# pufferswitch.net
KiCad netlist of a schematic drawn in EAGLE
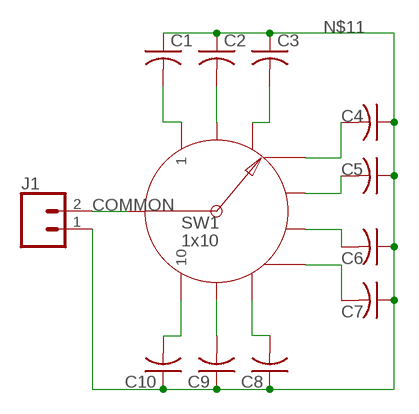
[diagram p0: schematic, sheet 1]

(export (version "E")
  (design (tool "Eeschema 10.0.6"))
  (components
    (comp (ref "C1")
      (value "C-US025-024X044")
      (footprint "eagle-import:C025-024X044")
      (libsource (lib "eagle-import") (part "C-US025-024X044"))
    )
    (comp (ref "C2")
      (value "C-US025-024X044")
      (footprint "eagle-import:C025-024X044")
      (libsource (lib "eagle-import") (part "C-US025-024X044"))
    )
    (comp (ref "C3")
      (value "C-US025-024X044")
      (footprint "eagle-import:C025-024X044")
      (libsource (lib "eagle-import") (part "C-US025-024X044"))
    )
    (comp (ref "C4")
      (value "C-US025-024X044")
      (footprint "eagle-import:C025-024X044")
      (libsource (lib "eagle-import") (part "C-US025-024X044"))
    )
    (comp (ref "C5")
      (value "C-US025-024X044")
      (footprint "eagle-import:C025-024X044")
      (libsource (lib "eagle-import") (part "C-US025-024X044"))
    )
    (comp (ref "C6")
      (value "C-US025-024X044")
      (footprint "eagle-import:C025-024X044")
      (libsource (lib "eagle-import") (part "C-US025-024X044"))
    )
    (comp (ref "C7")
      (value "C-US025-024X044")
      (footprint "eagle-import:C025-024X044")
      (libsource (lib "eagle-import") (part "C-US025-024X044"))
    )
    (comp (ref "C8")
      (value "C-US025-024X044")
      (footprint "eagle-import:C025-024X044")
      (libsource (lib "eagle-import") (part "C-US025-024X044"))
    )
    (comp (ref "C9")
      (value "C-US025-024X044")
      (footprint "eagle-import:C025-024X044")
      (libsource (lib "eagle-import") (part "C-US025-024X044"))
    )
    (comp (ref "C10")
      (value "C-US025-024X044")
      (footprint "eagle-import:C025-024X044")
      (libsource (lib "eagle-import") (part "C-US025-024X044"))
    )
    (comp (ref "J1")
      (value "CONN_02")
      (footprint "eagle-import:1X02")
      (libsource (lib "eagle-import") (part "CONN_02"))
    )
    (comp (ref "SW1")
      (value "1x10")
      (footprint "eagle-import:ROTARY_SWITCH_1X10_KIT")
      (libsource (lib "eagle-import") (part "SWITCH_ROTARY_1X10KIT"))
    )
  )
  (nets
    (net (code "1") (name "/COMMON") (class "Default")
      (node (ref "J1") (pin "2") (pinfunction "2_2") (pintype "passive"))
      (node (ref "SW1") (pin "COMMON") (pinfunction "COMMON_COMMON") (pintype "bidirectional"))
    )
    (net (code "2") (name "/N$11") (class "Default")
      (node (ref "C1") (pin "1") (pinfunction "1_1") (pintype "passive"))
      (node (ref "C10") (pin "1") (pinfunction "1_1") (pintype "passive"))
      (node (ref "C2") (pin "1") (pinfunction "1_1") (pintype "passive"))
      (node (ref "C3") (pin "1") (pinfunction "1_1") (pintype "passive"))
      (node (ref "C4") (pin "1") (pinfunction "1_1") (pintype "passive"))
      (node (ref "C5") (pin "1") (pinfunction "1_1") (pintype "passive"))
      (node (ref "C6") (pin "1") (pinfunction "1_1") (pintype "passive"))
      (node (ref "C7") (pin "1") (pinfunction "1_1") (pintype "passive"))
      (node (ref "C8") (pin "1") (pinfunction "1_1") (pintype "passive"))
      (node (ref "C9") (pin "1") (pinfunction "1_1") (pintype "passive"))
      (node (ref "J1") (pin "1") (pinfunction "1_1") (pintype "passive"))
    )
    (net (code "3") (name "Net-(C1-Pad2)") (class "Default")
      (node (ref "C1") (pin "2") (pinfunction "2_2") (pintype "passive"))
      (node (ref "SW1") (pin "1") (pinfunction "1_1") (pintype "bidirectional"))
    )
    (net (code "4") (name "Net-(C2-Pad2)") (class "Default")
      (node (ref "C2") (pin "2") (pinfunction "2_2") (pintype "passive"))
      (node (ref "SW1") (pin "2") (pinfunction "2_2") (pintype "bidirectional"))
    )
    (net (code "5") (name "Net-(C3-Pad2)") (class "Default")
      (node (ref "C3") (pin "2") (pinfunction "2_2") (pintype "passive"))
      (node (ref "SW1") (pin "3") (pinfunction "3_3") (pintype "bidirectional"))
    )
    (net (code "6") (name "Net-(C4-Pad2)") (class "Default")
      (node (ref "C4") (pin "2") (pinfunction "2_2") (pintype "passive"))
      (node (ref "SW1") (pin "4") (pinfunction "4_4") (pintype "bidirectional"))
    )
    (net (code "7") (name "Net-(C5-Pad2)") (class "Default")
      (node (ref "C5") (pin "2") (pinfunction "2_2") (pintype "passive"))
      (node (ref "SW1") (pin "5") (pinfunction "5_5") (pintype "bidirectional"))
    )
    (net (code "8") (name "Net-(C6-Pad2)") (class "Default")
      (node (ref "C6") (pin "2") (pinfunction "2_2") (pintype "passive"))
      (node (ref "SW1") (pin "6") (pinfunction "6_6") (pintype "bidirectional"))
    )
    (net (code "9") (name "Net-(C7-Pad2)") (class "Default")
      (node (ref "C7") (pin "2") (pinfunction "2_2") (pintype "passive"))
      (node (ref "SW1") (pin "7") (pinfunction "7_7") (pintype "bidirectional"))
    )
    (net (code "10") (name "Net-(C8-Pad2)") (class "Default")
      (node (ref "C8") (pin "2") (pinfunction "2_2") (pintype "passive"))
      (node (ref "SW1") (pin "8") (pinfunction "8_8") (pintype "bidirectional"))
    )
    (net (code "11") (name "Net-(C9-Pad2)") (class "Default")
      (node (ref "C9") (pin "2") (pinfunction "2_2") (pintype "passive"))
      (node (ref "SW1") (pin "9") (pinfunction "9_9") (pintype "bidirectional"))
    )
    (net (code "12") (name "Net-(C10-Pad2)") (class "Default")
      (node (ref "C10") (pin "2") (pinfunction "2_2") (pintype "passive"))
      (node (ref "SW1") (pin "10") (pinfunction "10_10") (pintype "bidirectional"))
    )
  )
)
